# PLL.net
KiCad netlist of a schematic drawn in Altium Designer
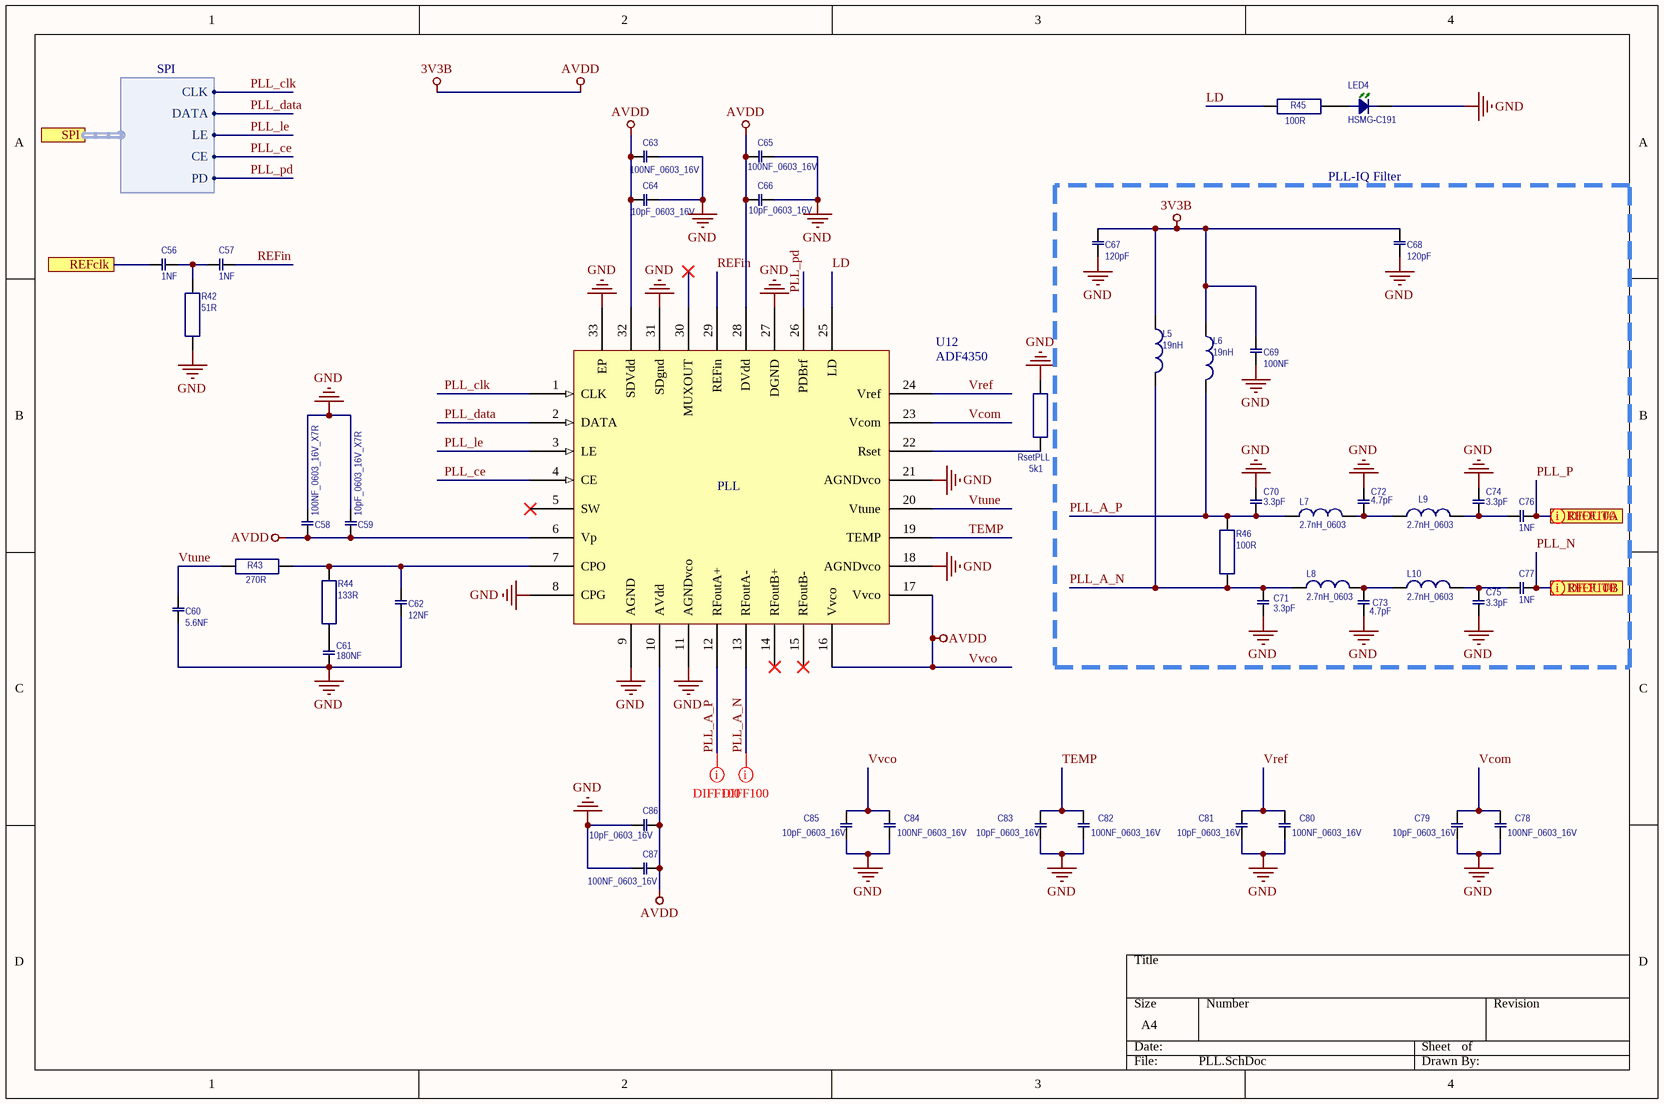
[diagram p0: PLL.SchDoc]

(export (version "E")
  (design (tool "Eeschema 10.0.6"))
  (components
    (comp (ref "C56")
      (value "1NF")
      (footprint "CAP0603")
      (description "128-8255    Capacitor MLC-X7R_0603_100NF_10%_50V; C0603C104K5RAC; KEMET; RoHS=Yes")
      (libsource (lib "ONEMULA_V2") (part "100NF_0603_50V_X7R"))
    )
    (comp (ref "C57")
      (value "1NF")
      (footprint "CAP0603")
      (description "128-8255    Capacitor MLC-X7R_0603_100NF_10%_50V; C0603C104K5RAC; KEMET; RoHS=Yes")
      (libsource (lib "ONEMULA_V2") (part "100NF_0603_50V_X7R"))
    )
    (comp (ref "C58")
      (value "100NF_0603_16V_X7R")
      (footprint "CAP0603")
      (description "128-8255    Capacitor MLC-X7R_0603_100NF_10%_50V; C0603C104K5RAC; KEMET; RoHS=Yes")
      (libsource (lib "ONEMULA_V2") (part "100NF_0603_50V_X7R"))
    )
    (comp (ref "C59")
      (value "10pF_0603_16V_X7R")
      (footprint "CAP0603")
      (description "128-8255    Capacitor MLC-X7R_0603_100NF_10%_50V; C0603C104K5RAC; KEMET; RoHS=Yes")
      (libsource (lib "ONEMULA_V2") (part "100NF_0603_50V_X7R"))
    )
    (comp (ref "C60")
      (value "5.6NF")
      (footprint "CAP0603")
      (description "128-8255    Capacitor MLC-X7R_0603_100NF_10%_50V; C0603C104K5RAC; KEMET; RoHS=Yes")
      (libsource (lib "ONEMULA_V2") (part "100NF_0603_50V_X7R"))
    )
    (comp (ref "C61")
      (value "180NF")
      (footprint "CAP0603")
      (description "128-8255    Capacitor MLC-X7R_0603_100NF_10%_50V; C0603C104K5RAC; KEMET; RoHS=Yes")
      (libsource (lib "ONEMULA_V2") (part "100NF_0603_50V_X7R"))
    )
    (comp (ref "C62")
      (value "12NF")
      (footprint "CAP0603")
      (description "128-8255    Capacitor MLC-X7R_0603_100NF_10%_50V; C0603C104K5RAC; KEMET; RoHS=Yes")
      (libsource (lib "ONEMULA_V2") (part "100NF_0603_50V_X7R"))
    )
    (comp (ref "C63")
      (value "100NF_0603_16V")
      (footprint "CAP0603")
      (description "128-8255    Capacitor MLC-X7R_0603_100NF_10%_50V; C0603C104K5RAC; KEMET; RoHS=Yes")
      (libsource (lib "ONEMULA_V2") (part "100NF_0603_50V_X7R"))
    )
    (comp (ref "C64")
      (value "10pF_0603_16V")
      (footprint "CAP0603")
      (description "128-8255    Capacitor MLC-X7R_0603_100NF_10%_50V; C0603C104K5RAC; KEMET; RoHS=Yes")
      (libsource (lib "ONEMULA_V2") (part "100NF_0603_50V_X7R"))
    )
    (comp (ref "C65")
      (value "100NF_0603_16V")
      (footprint "CAP0603")
      (description "128-8255    Capacitor MLC-X7R_0603_100NF_10%_50V; C0603C104K5RAC; KEMET; RoHS=Yes")
      (libsource (lib "ONEMULA_V2") (part "100NF_0603_50V_X7R"))
    )
    (comp (ref "C66")
      (value "10pF_0603_16V")
      (footprint "CAP0603")
      (description "128-8255    Capacitor MLC-X7R_0603_100NF_10%_50V; C0603C104K5RAC; KEMET; RoHS=Yes")
      (libsource (lib "ONEMULA_V2") (part "100NF_0603_50V_X7R"))
    )
    (comp (ref "C67")
      (value "120pF")
      (footprint "CAP0603")
      (description "141-4603    Capacitor MLC-NPO_0603_100PF_5%_50V; C0603C101J5GAC; KEMET; RoHS=Yes")
      (libsource (lib "ONEMULA_V2") (part "100PF_0603_50V_NP0"))
    )
    (comp (ref "C68")
      (value "120pF")
      (footprint "CAP0603")
      (description "141-4603    Capacitor MLC-NPO_0603_100PF_5%_50V; C0603C101J5GAC; KEMET; RoHS=Yes")
      (libsource (lib "ONEMULA_V2") (part "100PF_0603_50V_NP0"))
    )
    (comp (ref "C69")
      (value "100NF")
      (footprint "CAP0603")
      (description "128-8255    Capacitor MLC-X7R_0603_100NF_10%_50V; C0603C104K5RAC; KEMET; RoHS=Yes")
      (libsource (lib "ONEMULA_V2") (part "100NF_0603_50V_X7R"))
    )
    (comp (ref "C70")
      (value "3.3pF")
      (footprint "CAP0603")
      (description "141-4603    Capacitor MLC-NPO_0603_100PF_5%_50V; C0603C101J5GAC; KEMET; RoHS=Yes")
      (libsource (lib "ONEMULA_V2") (part "100PF_0603_50V_NP0"))
    )
    (comp (ref "C71")
      (value "3.3pF")
      (footprint "CAP0603")
      (description "141-4603    Capacitor MLC-NPO_0603_100PF_5%_50V; C0603C101J5GAC; KEMET; RoHS=Yes")
      (libsource (lib "ONEMULA_V2") (part "100PF_0603_50V_NP0"))
    )
    (comp (ref "C72")
      (value "4.7pF")
      (footprint "CAP0603")
      (description "141-4603    Capacitor MLC-NPO_0603_100PF_5%_50V; C0603C101J5GAC; KEMET; RoHS=Yes")
      (libsource (lib "ONEMULA_V2") (part "100PF_0603_50V_NP0"))
    )
    (comp (ref "C73")
      (value "4.7pF")
      (footprint "CAP0603")
      (description "141-4603    Capacitor MLC-NPO_0603_100PF_5%_50V; C0603C101J5GAC; KEMET; RoHS=Yes")
      (libsource (lib "ONEMULA_V2") (part "100PF_0603_50V_NP0"))
    )
    (comp (ref "C74")
      (value "3.3pF")
      (footprint "CAP0603")
      (description "141-4603    Capacitor MLC-NPO_0603_100PF_5%_50V; C0603C101J5GAC; KEMET; RoHS=Yes")
      (libsource (lib "ONEMULA_V2") (part "100PF_0603_50V_NP0"))
    )
    (comp (ref "C75")
      (value "3.3pF")
      (footprint "CAP0603")
      (description "141-4603    Capacitor MLC-NPO_0603_100PF_5%_50V; C0603C101J5GAC; KEMET; RoHS=Yes")
      (libsource (lib "ONEMULA_V2") (part "100PF_0603_50V_NP0"))
    )
    (comp (ref "C76")
      (value "1NF")
      (footprint "CAP0603")
      (description "128-8255    Capacitor MLC-X7R_0603_100NF_10%_50V; C0603C104K5RAC; KEMET; RoHS=Yes")
      (libsource (lib "ONEMULA_V2") (part "100NF_0603_50V_X7R"))
    )
    (comp (ref "C77")
      (value "1NF")
      (footprint "CAP0603")
      (description "128-8255    Capacitor MLC-X7R_0603_100NF_10%_50V; C0603C104K5RAC; KEMET; RoHS=Yes")
      (libsource (lib "ONEMULA_V2") (part "100NF_0603_50V_X7R"))
    )
    (comp (ref "C78")
      (value "100NF_0603_16V")
      (footprint "CAP0603")
      (description "128-8255    Capacitor MLC-X7R_0603_100NF_10%_50V; C0603C104K5RAC; KEMET; RoHS=Yes")
      (libsource (lib "ONEMULA_V2") (part "100NF_0603_50V_X7R"))
    )
    (comp (ref "C79")
      (value "10pF_0603_16V")
      (footprint "CAP0603")
      (description "128-8255    Capacitor MLC-X7R_0603_100NF_10%_50V; C0603C104K5RAC; KEMET; RoHS=Yes")
      (libsource (lib "ONEMULA_V2") (part "100NF_0603_50V_X7R"))
    )
    (comp (ref "C80")
      (value "100NF_0603_16V")
      (footprint "CAP0603")
      (description "128-8255    Capacitor MLC-X7R_0603_100NF_10%_50V; C0603C104K5RAC; KEMET; RoHS=Yes")
      (libsource (lib "ONEMULA_V2") (part "100NF_0603_50V_X7R"))
    )
    (comp (ref "C81")
      (value "10pF_0603_16V")
      (footprint "CAP0603")
      (description "128-8255    Capacitor MLC-X7R_0603_100NF_10%_50V; C0603C104K5RAC; KEMET; RoHS=Yes")
      (libsource (lib "ONEMULA_V2") (part "100NF_0603_50V_X7R"))
    )
    (comp (ref "C82")
      (value "100NF_0603_16V")
      (footprint "CAP0603")
      (description "128-8255    Capacitor MLC-X7R_0603_100NF_10%_50V; C0603C104K5RAC; KEMET; RoHS=Yes")
      (libsource (lib "ONEMULA_V2") (part "100NF_0603_50V_X7R"))
    )
    (comp (ref "C83")
      (value "10pF_0603_16V")
      (footprint "CAP0603")
      (description "128-8255    Capacitor MLC-X7R_0603_100NF_10%_50V; C0603C104K5RAC; KEMET; RoHS=Yes")
      (libsource (lib "ONEMULA_V2") (part "100NF_0603_50V_X7R"))
    )
    (comp (ref "C84")
      (value "100NF_0603_16V")
      (footprint "CAP0603")
      (description "128-8255    Capacitor MLC-X7R_0603_100NF_10%_50V; C0603C104K5RAC; KEMET; RoHS=Yes")
      (libsource (lib "ONEMULA_V2") (part "100NF_0603_50V_X7R"))
    )
    (comp (ref "C85")
      (value "10pF_0603_16V")
      (footprint "CAP0603")
      (description "128-8255    Capacitor MLC-X7R_0603_100NF_10%_50V; C0603C104K5RAC; KEMET; RoHS=Yes")
      (libsource (lib "ONEMULA_V2") (part "100NF_0603_50V_X7R"))
    )
    (comp (ref "C86")
      (value "10pF_0603_16V")
      (footprint "CAP0603")
      (description "128-8255    Capacitor MLC-X7R_0603_100NF_10%_50V; C0603C104K5RAC; KEMET; RoHS=Yes")
      (libsource (lib "ONEMULA_V2") (part "100NF_0603_50V_X7R"))
    )
    (comp (ref "C87")
      (value "100NF_0603_16V")
      (footprint "CAP0603")
      (description "128-8255    Capacitor MLC-X7R_0603_100NF_10%_50V; C0603C104K5RAC; KEMET; RoHS=Yes")
      (libsource (lib "ONEMULA_V2") (part "100NF_0603_50V_X7R"))
    )
    (comp (ref "L5") (value "19nH") (footprint "0603") (libsource (lib "My_library") (part "Inductor0603")))
    (comp (ref "L6") (value "19nH") (footprint "0603") (libsource (lib "My_library") (part "Inductor0603")))
    (comp (ref "L7")
      (value "2.7nH_0603")
      (footprint "0603")
      (libsource (lib "My_library") (part "Inductor0603"))
    )
    (comp (ref "L8")
      (value "2.7nH_0603")
      (footprint "0603")
      (libsource (lib "My_library") (part "Inductor0603"))
    )
    (comp (ref "L9")
      (value "2.7nH_0603")
      (footprint "0603")
      (libsource (lib "My_library") (part "Inductor0603"))
    )
    (comp (ref "L10")
      (value "2.7nH_0603")
      (footprint "0603")
      (libsource (lib "My_library") (part "Inductor0603"))
    )
    (comp (ref "LED4")
      (value "HSMG-C191")
      (footprint "D0603")
      (description "855-4617    LED DIODE GREEN 20mA, 0603; HSMG-C191; AVAGO TECHNOLOGIES; RoHS=Yes")
      (libsource (lib "ONEMULA_V2") (part "HSMG-C191"))
    )
    (comp (ref "R42")
      (value "51R")
      (footprint "R0603")
      (description "165-2832    RESISTOR MF_0603_120R_0.1W_1%_75V; CRCW0603120RFKEA; VISHAY; RoHS=Yes")
      (libsource (lib "ONEMULA_V2") (part "120R_0603_0.1W_1%"))
    )
    (comp (ref "R43")
      (value "270R")
      (footprint "R0603")
      (description "146-9752    RESISTOR MF_0603_100R_0.1W_1%_75V; CRCW0603100RFKEA; VISHAY; RoHS=Yes")
      (libsource (lib "ONEMULA_V2") (part "100R_0603_0.1W_1%"))
    )
    (comp (ref "R44")
      (value "133R")
      (footprint "R0603")
      (description "146-9752    RESISTOR MF_0603_100R_0.1W_1%_75V; CRCW0603100RFKEA; VISHAY; RoHS=Yes")
      (libsource (lib "ONEMULA_V2") (part "100R_0603_0.1W_1%"))
    )
    (comp (ref "R45")
      (value "100R")
      (footprint "R0603")
      (description "923-3130    RESISTOR MF_0603_0.0R_0.1W_50V; RC0603JR-070RL; YAGEO; RoHS=Yes")
      (libsource (lib "ONEMULA_V2") (part "0.0R_0603_0.063W_5%"))
    )
    (comp (ref "R46")
      (value "100R")
      (footprint "R0603")
      (description "146-9752    RESISTOR MF_0603_100R_0.1W_1%_75V; CRCW0603100RFKEA; VISHAY; RoHS=Yes")
      (libsource (lib "ONEMULA_V2") (part "100R_0603_0.1W_1%"))
    )
    (comp (ref "RsetPLL")
      (value "5k1")
      (footprint "R0603")
      (description "146-9807    RESISTOR MF_0603_4K7_0.1W_1%_75V; CRCW06034K70FKEA; VISHAY; RoHS=Yes")
      (libsource (lib "ONEMULA_V2") (part "4K7_0603_0.1W_1%"))
    )
    (comp (ref "U12") (value "ADF4350") (footprint "LFCSP8") (libsource (lib "My_library") (part "ADF4150")))
  )
  (nets
    (net (code "2") (name "/LD") (class "Default")
      (node (ref "R45") (pin "1") (pinfunction "1_1") (pintype "passive"))
      (node (ref "U12") (pin "25") (pinfunction "LD_25") (pintype "passive"))
    )
    (net (code "3") (name "/PLL_A_N") (class "Default")
      (node (ref "C71") (pin "1") (pinfunction "1_1") (pintype "passive"))
      (node (ref "L5") (pin "2") (pinfunction "2_2") (pintype "passive"))
      (node (ref "L8") (pin "1") (pinfunction "1_1") (pintype "passive"))
      (node (ref "R46") (pin "1") (pinfunction "1_1") (pintype "passive"))
      (node (ref "U12") (pin "13") (pinfunction "RFoutA-_13") (pintype "passive"))
    )
    (net (code "4") (name "/PLL_A_P") (class "Default")
      (node (ref "C70") (pin "2") (pinfunction "2_2") (pintype "passive"))
      (node (ref "L6") (pin "2") (pinfunction "2_2") (pintype "passive"))
      (node (ref "L7") (pin "1") (pinfunction "1_1") (pintype "passive"))
      (node (ref "R46") (pin "2") (pinfunction "2_2") (pintype "passive"))
      (node (ref "U12") (pin "12") (pinfunction "RFoutA+_12") (pintype "passive"))
    )
    (net (code "5") (name "/PLL_N") (class "Default")
      (node (ref "C77") (pin "2") (pinfunction "2_2") (pintype "passive"))
    )
    (net (code "6") (name "/PLL_P") (class "Default")
      (node (ref "C76") (pin "2") (pinfunction "2_2") (pintype "passive"))
    )
    (net (code "7") (name "/PLL_ce") (class "Default")
      (node (ref "U12") (pin "4") (pinfunction "CE_4") (pintype "input"))
    )
    (net (code "8") (name "/PLL_clk") (class "Default")
      (node (ref "U12") (pin "1") (pinfunction "CLK_1") (pintype "input"))
    )
    (net (code "9") (name "/PLL_data") (class "Default")
      (node (ref "U12") (pin "2") (pinfunction "DATA_2") (pintype "input"))
    )
    (net (code "10") (name "/PLL_le") (class "Default")
      (node (ref "U12") (pin "3") (pinfunction "LE_3") (pintype "input"))
    )
    (net (code "11") (name "/PLL_pd") (class "Default")
      (node (ref "U12") (pin "26") (pinfunction "PDBrf_26") (pintype "passive"))
    )
    (net (code "12") (name "/REFclk") (class "Default")
      (node (ref "C56") (pin "1") (pinfunction "1_1") (pintype "passive"))
    )
    (net (code "13") (name "/REFin") (class "Default")
      (node (ref "C57") (pin "2") (pinfunction "2_2") (pintype "passive"))
      (node (ref "U12") (pin "29") (pinfunction "REFin_29") (pintype "passive"))
    )
    (net (code "14") (name "/TEMP") (class "Default")
      (node (ref "C82") (pin "1") (pinfunction "1_1") (pintype "passive"))
      (node (ref "C83") (pin "1") (pinfunction "1_1") (pintype "passive"))
      (node (ref "U12") (pin "19") (pinfunction "TEMP_19") (pintype "passive"))
    )
    (net (code "15") (name "/Vcom") (class "Default")
      (node (ref "C78") (pin "1") (pinfunction "1_1") (pintype "passive"))
      (node (ref "C79") (pin "1") (pinfunction "1_1") (pintype "passive"))
      (node (ref "U12") (pin "23") (pinfunction "Vcom_23") (pintype "passive"))
    )
    (net (code "16") (name "/Vref") (class "Default")
      (node (ref "C80") (pin "1") (pinfunction "1_1") (pintype "passive"))
      (node (ref "C81") (pin "1") (pinfunction "1_1") (pintype "passive"))
      (node (ref "U12") (pin "24") (pinfunction "Vref_24") (pintype "passive"))
    )
    (net (code "17") (name "/Vtune") (class "Default")
      (node (ref "C60") (pin "1") (pinfunction "1_1") (pintype "passive"))
      (node (ref "R43") (pin "2") (pinfunction "2_2") (pintype "passive"))
      (node (ref "U12") (pin "20") (pinfunction "Vtune_20") (pintype "passive"))
    )
    (net (code "19") (name "3V3B") (class "Default")
      (node (ref "C58") (pin "1") (pinfunction "1_1") (pintype "passive"))
      (node (ref "C59") (pin "1") (pinfunction "1_1") (pintype "passive"))
      (node (ref "C63") (pin "1") (pinfunction "1_1") (pintype "passive"))
      (node (ref "C64") (pin "1") (pinfunction "1_1") (pintype "passive"))
      (node (ref "C65") (pin "1") (pinfunction "1_1") (pintype "passive"))
      (node (ref "C66") (pin "1") (pinfunction "1_1") (pintype "passive"))
      (node (ref "C67") (pin "1") (pinfunction "1_1") (pintype "passive"))
      (node (ref "C68") (pin "1") (pinfunction "1_1") (pintype "passive"))
      (node (ref "C69") (pin "1") (pinfunction "1_1") (pintype "passive"))
      (node (ref "C84") (pin "1") (pinfunction "1_1") (pintype "passive"))
      (node (ref "C85") (pin "1") (pinfunction "1_1") (pintype "passive"))
      (node (ref "C86") (pin "1") (pinfunction "1_1") (pintype "passive"))
      (node (ref "C87") (pin "1") (pinfunction "1_1") (pintype "passive"))
      (node (ref "L5") (pin "1") (pinfunction "1_1") (pintype "passive"))
      (node (ref "L6") (pin "1") (pinfunction "1_1") (pintype "passive"))
      (node (ref "U12") (pin "10") (pinfunction "AVdd_10") (pintype "passive"))
      (node (ref "U12") (pin "16") (pinfunction "Vvco_16") (pintype "passive"))
      (node (ref "U12") (pin "17") (pinfunction "Vvco_17") (pintype "passive"))
      (node (ref "U12") (pin "28") (pinfunction "DVdd_28") (pintype "passive"))
      (node (ref "U12") (pin "32") (pinfunction "SDVdd_32") (pintype "passive"))
      (node (ref "U12") (pin "6") (pinfunction "Vp_6") (pintype "passive"))
    )
    (net (code "20") (name "GND") (class "Default")
      (node (ref "C58") (pin "2") (pinfunction "2_2") (pintype "passive"))
      (node (ref "C59") (pin "2") (pinfunction "2_2") (pintype "passive"))
      (node (ref "C60") (pin "2") (pinfunction "2_2") (pintype "passive"))
      (node (ref "C61") (pin "2") (pinfunction "2_2") (pintype "passive"))
      (node (ref "C62") (pin "2") (pinfunction "2_2") (pintype "passive"))
      (node (ref "C63") (pin "2") (pinfunction "2_2") (pintype "passive"))
      (node (ref "C64") (pin "2") (pinfunction "2_2") (pintype "passive"))
      (node (ref "C65") (pin "2") (pinfunction "2_2") (pintype "passive"))
      (node (ref "C66") (pin "2") (pinfunction "2_2") (pintype "passive"))
      (node (ref "C67") (pin "2") (pinfunction "2_2") (pintype "passive"))
      (node (ref "C68") (pin "2") (pinfunction "2_2") (pintype "passive"))
      (node (ref "C69") (pin "2") (pinfunction "2_2") (pintype "passive"))
      (node (ref "C70") (pin "1") (pinfunction "1_1") (pintype "passive"))
      (node (ref "C71") (pin "2") (pinfunction "2_2") (pintype "passive"))
      (node (ref "C72") (pin "1") (pinfunction "1_1") (pintype "passive"))
      (node (ref "C73") (pin "2") (pinfunction "2_2") (pintype "passive"))
      (node (ref "C74") (pin "1") (pinfunction "1_1") (pintype "passive"))
      (node (ref "C75") (pin "2") (pinfunction "2_2") (pintype "passive"))
      (node (ref "C78") (pin "2") (pinfunction "2_2") (pintype "passive"))
      (node (ref "C79") (pin "2") (pinfunction "2_2") (pintype "passive"))
      (node (ref "C80") (pin "2") (pinfunction "2_2") (pintype "passive"))
      (node (ref "C81") (pin "2") (pinfunction "2_2") (pintype "passive"))
      (node (ref "C82") (pin "2") (pinfunction "2_2") (pintype "passive"))
      (node (ref "C83") (pin "2") (pinfunction "2_2") (pintype "passive"))
      (node (ref "C84") (pin "2") (pinfunction "2_2") (pintype "passive"))
      (node (ref "C85") (pin "2") (pinfunction "2_2") (pintype "passive"))
      (node (ref "C86") (pin "2") (pinfunction "2_2") (pintype "passive"))
      (node (ref "C87") (pin "2") (pinfunction "2_2") (pintype "passive"))
      (node (ref "LED4") (pin "K") (pinfunction "K_K") (pintype "passive"))
      (node (ref "R42") (pin "1") (pinfunction "1_1") (pintype "passive"))
      (node (ref "RsetPLL") (pin "1") (pinfunction "1_1") (pintype "passive"))
      (node (ref "U12") (pin "11") (pinfunction "AGNDvco_11") (pintype "passive"))
      (node (ref "U12") (pin "18") (pinfunction "AGNDvco_18") (pintype "passive"))
      (node (ref "U12") (pin "21") (pinfunction "AGNDvco_21") (pintype "passive"))
      (node (ref "U12") (pin "27") (pinfunction "DGND_27") (pintype "passive"))
      (node (ref "U12") (pin "31") (pinfunction "SDgnd_31") (pintype "passive"))
      (node (ref "U12") (pin "33") (pinfunction "EP_33") (pintype "passive"))
      (node (ref "U12") (pin "8") (pinfunction "CPG_8") (pintype "passive"))
      (node (ref "U12") (pin "9") (pinfunction "AGND_9") (pintype "passive"))
    )
    (net (code "21") (name "Net-(C56-Pad2)") (class "Default")
      (node (ref "C56") (pin "2") (pinfunction "2_2") (pintype "passive"))
      (node (ref "C57") (pin "1") (pinfunction "1_1") (pintype "passive"))
      (node (ref "R42") (pin "2") (pinfunction "2_2") (pintype "passive"))
    )
    (net (code "22") (name "Net-(C61-Pad1)") (class "Default")
      (node (ref "C61") (pin "1") (pinfunction "1_1") (pintype "passive"))
      (node (ref "R44") (pin "1") (pinfunction "1_1") (pintype "passive"))
    )
    (net (code "23") (name "Net-(C72-Pad2)") (class "Default")
      (node (ref "C72") (pin "2") (pinfunction "2_2") (pintype "passive"))
      (node (ref "L7") (pin "2") (pinfunction "2_2") (pintype "passive"))
      (node (ref "L9") (pin "1") (pinfunction "1_1") (pintype "passive"))
    )
    (net (code "24") (name "Net-(C73-Pad1)") (class "Default")
      (node (ref "C73") (pin "1") (pinfunction "1_1") (pintype "passive"))
      (node (ref "L10") (pin "1") (pinfunction "1_1") (pintype "passive"))
      (node (ref "L8") (pin "2") (pinfunction "2_2") (pintype "passive"))
    )
    (net (code "25") (name "Net-(C74-Pad2)") (class "Default")
      (node (ref "C74") (pin "2") (pinfunction "2_2") (pintype "passive"))
      (node (ref "C76") (pin "1") (pinfunction "1_1") (pintype "passive"))
      (node (ref "L9") (pin "2") (pinfunction "2_2") (pintype "passive"))
    )
    (net (code "26") (name "Net-(C75-Pad1)") (class "Default")
      (node (ref "C75") (pin "1") (pinfunction "1_1") (pintype "passive"))
      (node (ref "C77") (pin "1") (pinfunction "1_1") (pintype "passive"))
      (node (ref "L10") (pin "2") (pinfunction "2_2") (pintype "passive"))
    )
    (net (code "27") (name "Net-(LED4-PadA)") (class "Default")
      (node (ref "LED4") (pin "A") (pinfunction "A_A") (pintype "passive"))
      (node (ref "R45") (pin "2") (pinfunction "2_2") (pintype "passive"))
    )
    (net (code "28") (name "Net-(U12-CPO)") (class "Default")
      (node (ref "C62") (pin "1") (pinfunction "1_1") (pintype "passive"))
      (node (ref "R43") (pin "1") (pinfunction "1_1") (pintype "passive"))
      (node (ref "R44") (pin "2") (pinfunction "2_2") (pintype "passive"))
      (node (ref "U12") (pin "7") (pinfunction "CPO_7") (pintype "passive"))
    )
    (net (code "29") (name "Net-(U12-Rset)") (class "Default")
      (node (ref "RsetPLL") (pin "2") (pinfunction "2_2") (pintype "passive"))
      (node (ref "U12") (pin "22") (pinfunction "Rset_22") (pintype "passive"))
    )
    (net (code "30") (name "unconnected-(U12-MUXOUT-Pad30)") (class "Default")
      (node (ref "U12") (pin "30") (pinfunction "MUXOUT_30") (pintype "passive+no_connect"))
    )
    (net (code "31") (name "unconnected-(U12-RFoutB+-Pad14)") (class "Default")
      (node (ref "U12") (pin "14") (pinfunction "RFoutB+_14") (pintype "passive+no_connect"))
    )
    (net (code "32") (name "unconnected-(U12-RFoutB--Pad15)") (class "Default")
      (node (ref "U12") (pin "15") (pinfunction "RFoutB-_15") (pintype "passive+no_connect"))
    )
    (net (code "33") (name "unconnected-(U12-SW-Pad5)") (class "Default")
      (node (ref "U12") (pin "5") (pinfunction "SW_5") (pintype "passive+no_connect"))
    )
  )
)
